# SCH_Line-Follower-Circuit_2025-12-18.net
KiCad netlist of a schematic drawn in EasyEDA
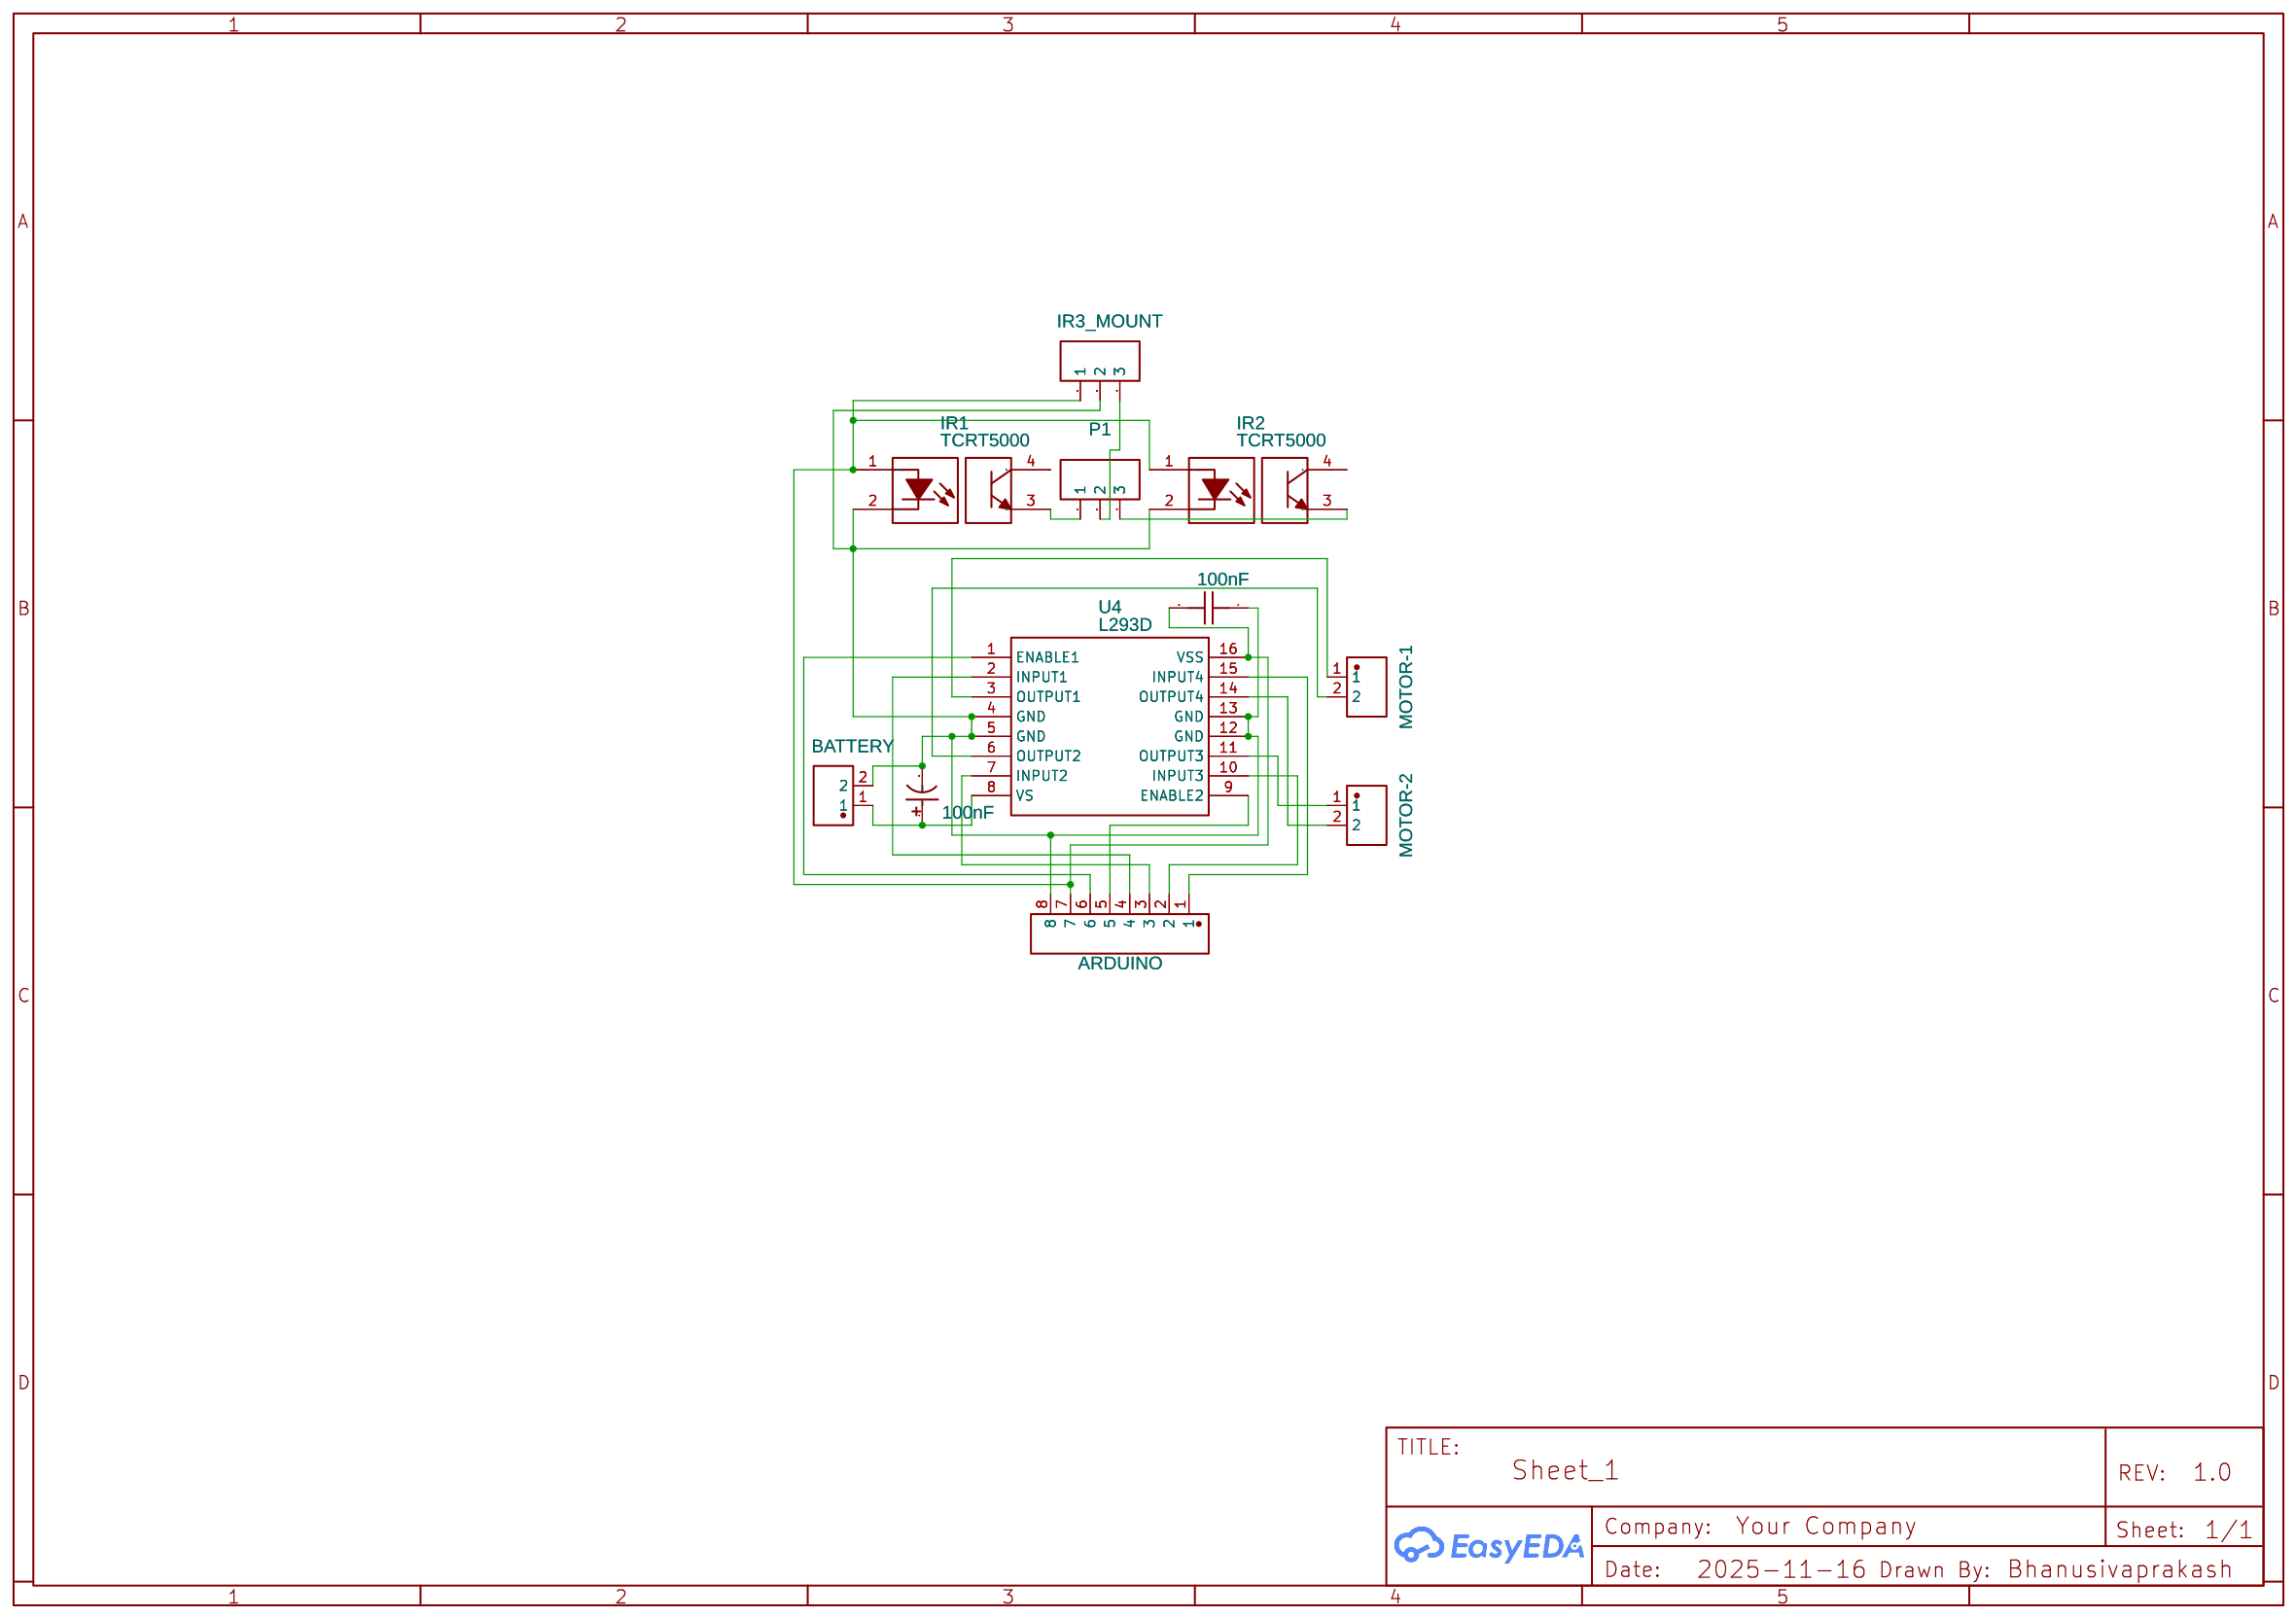
[diagram p0: schematic sheet]

(export (version "E")
  (design (tool "Eeschema 10.0.6"))
  (components
    (comp (ref "ARDUINO")
      (value "X6511FV-08-C85D32")
      (fields (field (name "Manufacturer") "XKB Connection(中国星坤)"))
      (libsource (lib "") (part "X6511FV-08-C85D32"))
    )
    (comp (ref "BATTERY")
      (value "KF301-5.0-2P")
      (fields (field (name "Manufacturer") "KEFA(科发)"))
      (libsource (lib "") (part "KF301-5.0-2P_1"))
    )
    (comp (ref "C1")
      (value "100nF")
      (fields
        (field (name "Manufacturer Part") "KM476M016D11RR0VH2FP0")
        (field (name "Manufacturer") "Chengx(承兴)")
      )
      (libsource (lib "") (part "47uF 16V Aluminum electrolytic capacitors"))
    )
    (comp (ref "IR1")
      (value "TCRT5000")
      (fields (field (name "Manufacturer") "VISHAY(威世)"))
      (libsource (lib "") (part "TCRT5000"))
    )
    (comp (ref "IR2")
      (value "TCRT5000")
      (fields (field (name "Manufacturer") "VISHAY(威世)"))
      (libsource (lib "") (part "TCRT5000"))
    )
    (comp (ref "IR3_MOUNT")
      (value "Header-Female-2.54_1x3")
      (fields (field (name "Manufacturer Part") "2.54-1*3P母") (field (name "Manufacturer") "BOOMELE(博穆精密)"))
      (libsource (lib "") (part "Header-Female-2.54_1x3_1"))
    )
    (comp (ref "MOTOR-1")
      (value "KF301-5.0-2P")
      (fields (field (name "Manufacturer") "KEFA(科发)"))
      (libsource (lib "") (part "KF301-5.0-2P"))
    )
    (comp (ref "MOTOR-2")
      (value "KF301-5.0-2P")
      (fields (field (name "Manufacturer") "KEFA(科发)"))
      (libsource (lib "") (part "KF301-5.0-2P"))
    )
    (comp (ref "P1")
      (value "Header-Female-2.54_1x3")
      (fields (field (name "Manufacturer Part") "2.54-1*3P母") (field (name "Manufacturer") "BOOMELE(博穆精密)"))
      (libsource (lib "") (part "Header-Female-2.54_1x3"))
    )
    (comp (ref "U4")
      (value "L293D")
      (fields (field (name "Manufacturer") "ST(意法半导体)"))
      (libsource (lib "") (part "L293D"))
    )
    (comp (ref "U5")
      (value "100nF")
      (fields (field (name "Manufacturer Part") "GRM155R71E103KA01D | SMD Ceramic Capacitor"))
      (libsource (lib "") (part "GRM155R71E103KA01D | SMD CERAMIC CAPACITOR"))
    )
  )
  (nets
    (net (code "1") (name "Net-(ARDUINO-Pad8)") (class "Default")
      (node (ref "ARDUINO") (pin "8") (pinfunction "8_8") (pintype "unspecified"))
      (node (ref "BATTERY") (pin "2") (pinfunction "2_2") (pintype "unspecified"))
      (node (ref "C1") (pin "2") (pinfunction "2_2") (pintype "input"))
      (node (ref "IR1") (pin "2") (pinfunction "2_2") (pintype "unspecified"))
      (node (ref "IR2") (pin "2") (pinfunction "2_2") (pintype "unspecified"))
      (node (ref "IR3_MOUNT") (pin "2") (pinfunction "2_2") (pintype "input"))
      (node (ref "U4") (pin "12") (pinfunction "GND_12") (pintype "unspecified"))
      (node (ref "U4") (pin "13") (pinfunction "GND_13") (pintype "unspecified"))
      (node (ref "U4") (pin "4") (pinfunction "GND_4") (pintype "unspecified"))
      (node (ref "U4") (pin "5") (pinfunction "GND_5") (pintype "unspecified"))
      (node (ref "U5") (pin "1") (pinfunction "1_1") (pintype "unspecified"))
    )
    (net (code "2") (name "Net-(IR1-Pad3)") (class "Default")
      (node (ref "IR1") (pin "3") (pinfunction "3_3") (pintype "unspecified"))
      (node (ref "P1") (pin "1") (pinfunction "1_1") (pintype "input"))
    )
    (net (code "3") (name "Net-(IR2-Pad3)") (class "Default")
      (node (ref "IR2") (pin "3") (pinfunction "3_3") (pintype "unspecified"))
      (node (ref "P1") (pin "3") (pinfunction "3_3") (pintype "input"))
    )
    (net (code "4") (name "Net-(IR3_MOUNT-Pad3)") (class "Default")
      (node (ref "IR3_MOUNT") (pin "3") (pinfunction "3_3") (pintype "input"))
      (node (ref "P1") (pin "2") (pinfunction "2_2") (pintype "input"))
    )
    (net (code "5") (name "Net-(U4-ENABLE1)") (class "Default")
      (node (ref "ARDUINO") (pin "6") (pinfunction "6_6") (pintype "unspecified"))
      (node (ref "U4") (pin "1") (pinfunction "ENABLE1_1") (pintype "unspecified"))
    )
    (net (code "6") (name "Net-(U4-ENABLE2)") (class "Default")
      (node (ref "ARDUINO") (pin "5") (pinfunction "5_5") (pintype "unspecified"))
      (node (ref "U4") (pin "9") (pinfunction "ENABLE2_9") (pintype "unspecified"))
    )
    (net (code "7") (name "Net-(U4-INPUT1)") (class "Default")
      (node (ref "ARDUINO") (pin "4") (pinfunction "4_4") (pintype "unspecified"))
      (node (ref "U4") (pin "2") (pinfunction "INPUT1_2") (pintype "unspecified"))
    )
    (net (code "8") (name "Net-(U4-INPUT2)") (class "Default")
      (node (ref "ARDUINO") (pin "3") (pinfunction "3_3") (pintype "unspecified"))
      (node (ref "U4") (pin "7") (pinfunction "INPUT2_7") (pintype "unspecified"))
    )
    (net (code "9") (name "Net-(U4-INPUT3)") (class "Default")
      (node (ref "ARDUINO") (pin "2") (pinfunction "2_2") (pintype "unspecified"))
      (node (ref "U4") (pin "10") (pinfunction "INPUT3_10") (pintype "unspecified"))
    )
    (net (code "10") (name "Net-(U4-INPUT4)") (class "Default")
      (node (ref "ARDUINO") (pin "1") (pinfunction "1_1") (pintype "unspecified"))
      (node (ref "U4") (pin "15") (pinfunction "INPUT4_15") (pintype "unspecified"))
    )
    (net (code "11") (name "Net-(U4-OUTPUT1)") (class "Default")
      (node (ref "MOTOR-1") (pin "1") (pinfunction "1_1") (pintype "unspecified"))
      (node (ref "U4") (pin "3") (pinfunction "OUTPUT1_3") (pintype "unspecified"))
    )
    (net (code "12") (name "Net-(U4-OUTPUT2)") (class "Default")
      (node (ref "MOTOR-1") (pin "2") (pinfunction "2_2") (pintype "unspecified"))
      (node (ref "U4") (pin "6") (pinfunction "OUTPUT2_6") (pintype "unspecified"))
    )
    (net (code "13") (name "Net-(U4-OUTPUT3)") (class "Default")
      (node (ref "MOTOR-2") (pin "1") (pinfunction "1_1") (pintype "unspecified"))
      (node (ref "U4") (pin "11") (pinfunction "OUTPUT3_11") (pintype "unspecified"))
    )
    (net (code "14") (name "Net-(U4-OUTPUT4)") (class "Default")
      (node (ref "MOTOR-2") (pin "2") (pinfunction "2_2") (pintype "unspecified"))
      (node (ref "U4") (pin "14") (pinfunction "OUTPUT4_14") (pintype "unspecified"))
    )
    (net (code "15") (name "Net-(U4-VS)") (class "Default")
      (node (ref "BATTERY") (pin "1") (pinfunction "1_1") (pintype "unspecified"))
      (node (ref "C1") (pin "1") (pinfunction "1_1") (pintype "input"))
      (node (ref "U4") (pin "8") (pinfunction "VS_8") (pintype "unspecified"))
    )
    (net (code "16") (name "Net-(U4-VSS)") (class "Default")
      (node (ref "ARDUINO") (pin "7") (pinfunction "7_7") (pintype "unspecified"))
      (node (ref "IR1") (pin "1") (pinfunction "1_1") (pintype "unspecified"))
      (node (ref "IR2") (pin "1") (pinfunction "1_1") (pintype "unspecified"))
      (node (ref "IR3_MOUNT") (pin "1") (pinfunction "1_1") (pintype "input"))
      (node (ref "U4") (pin "16") (pinfunction "VSS_16") (pintype "unspecified"))
      (node (ref "U5") (pin "2") (pinfunction "2_2") (pintype "unspecified"))
    )
    (net (code "17") (name "unconnected-(IR1-Pad4)") (class "Default")
      (node (ref "IR1") (pin "4") (pinfunction "4_4") (pintype "unspecified"))
    )
    (net (code "18") (name "unconnected-(IR2-Pad4)") (class "Default")
      (node (ref "IR2") (pin "4") (pinfunction "4_4") (pintype "unspecified"))
    )
  )
)
